# USB-CAN_v0_1.net
KiCad netlist of a schematic drawn in EAGLE
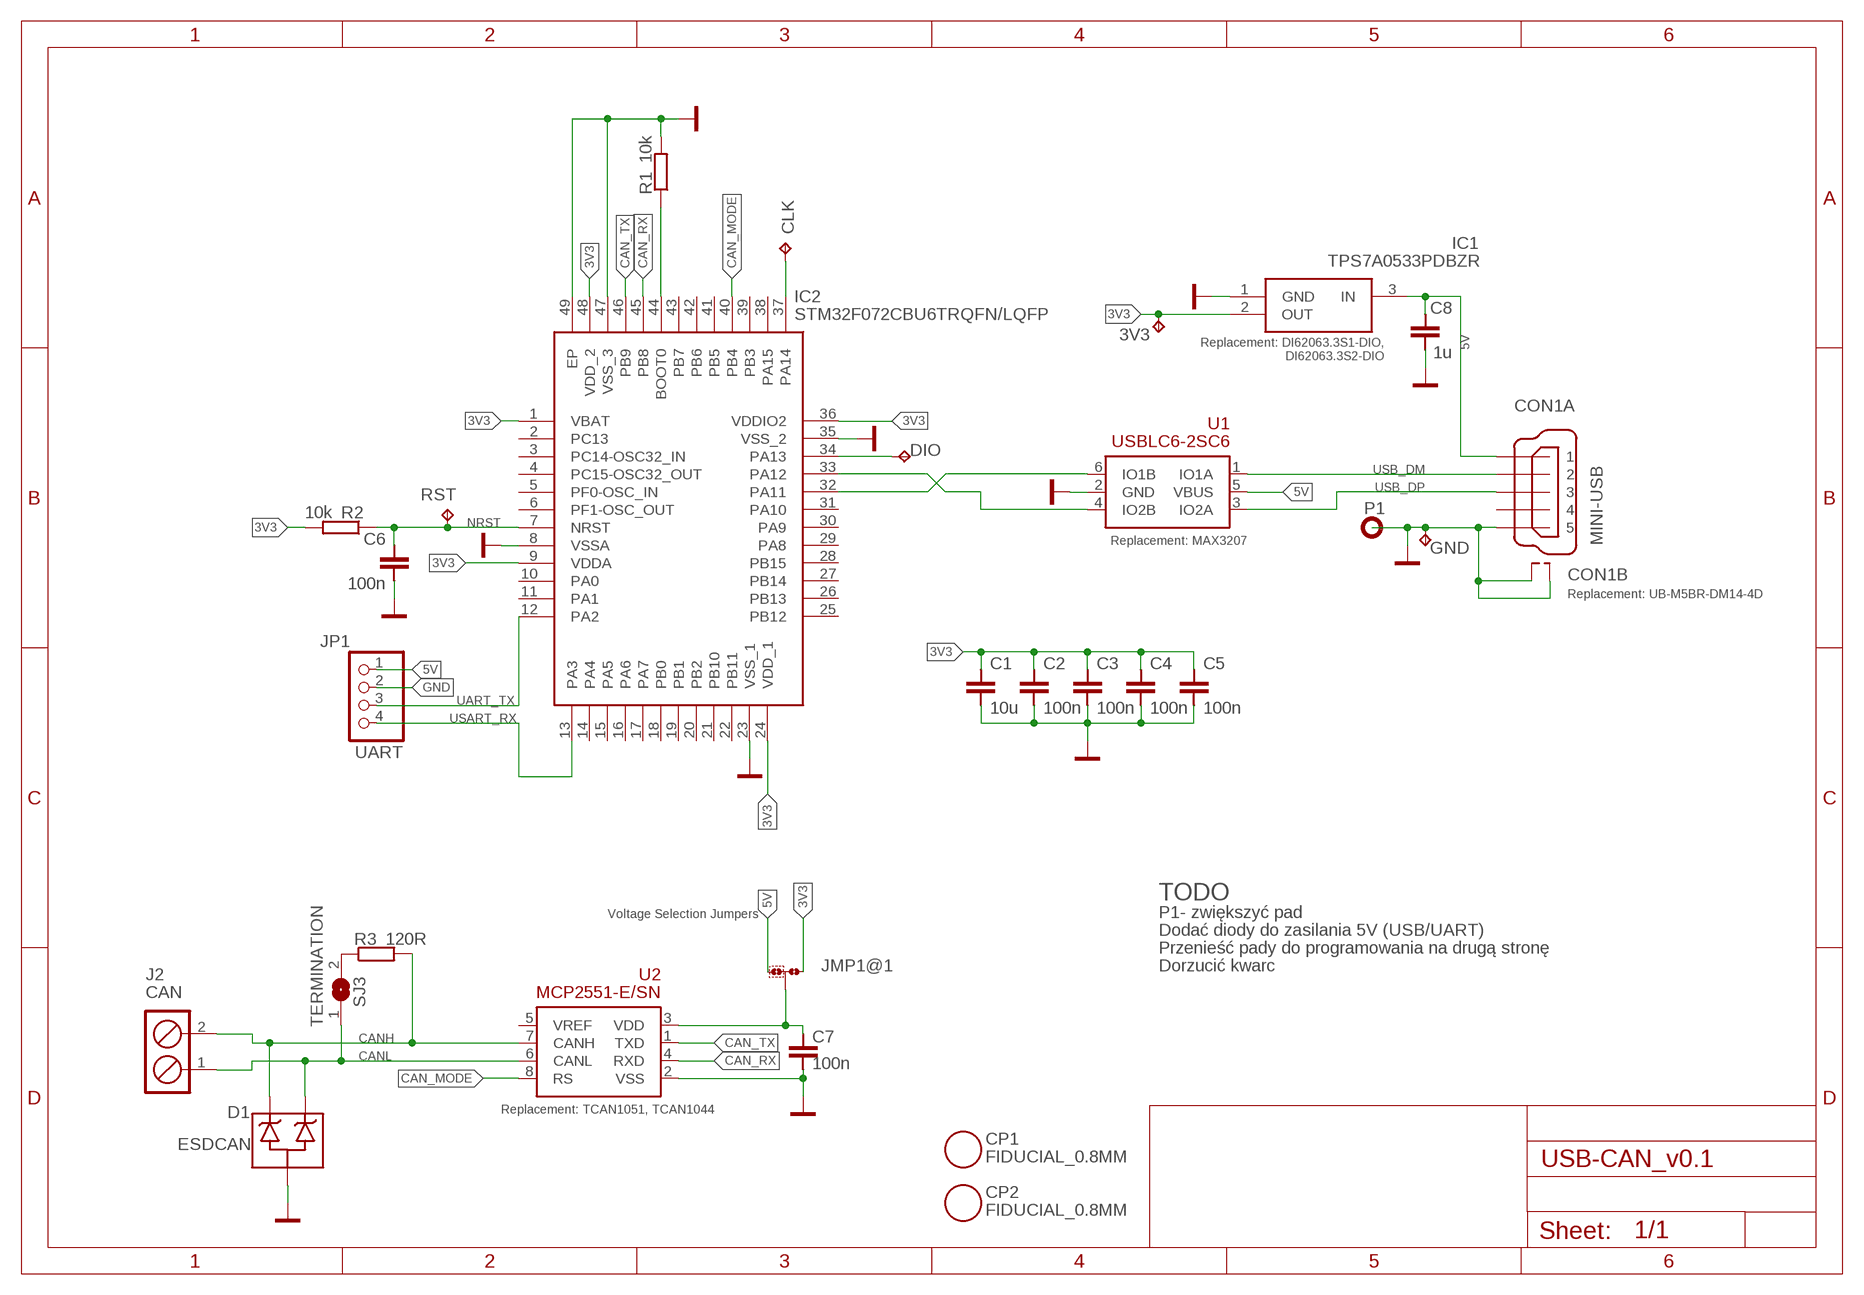
[diagram p0: schematic, sheet 1]

(export (version "E")
  (design (tool "Eeschema 10.0.6"))
  (components
    (comp (ref "3V3")
      (value "TPTP14R")
      (footprint "eagle-import:TP14R")
      (libsource (lib "eagle-import") (part "TPTP14R"))
    )
    (comp (ref "C1")
      (value "10u")
      (footprint "eagle-import:0603")
      (libsource (lib "eagle-import") (part "CAP_H-0603"))
    )
    (comp (ref "C2")
      (value "100n")
      (footprint "eagle-import:0603")
      (libsource (lib "eagle-import") (part "CAP_H-0603"))
    )
    (comp (ref "C3")
      (value "100n")
      (footprint "eagle-import:0603")
      (libsource (lib "eagle-import") (part "CAP_H-0603"))
    )
    (comp (ref "C4")
      (value "100n")
      (footprint "eagle-import:0603")
      (libsource (lib "eagle-import") (part "CAP_H-0603"))
    )
    (comp (ref "C5")
      (value "100n")
      (footprint "eagle-import:0603")
      (libsource (lib "eagle-import") (part "CAP_H-0603"))
    )
    (comp (ref "C6")
      (value "100n")
      (footprint "eagle-import:0603")
      (libsource (lib "eagle-import") (part "CAP_H-0603"))
    )
    (comp (ref "C7")
      (value "100n")
      (footprint "eagle-import:0603")
      (libsource (lib "eagle-import") (part "CAP_H-0603"))
    )
    (comp (ref "C8")
      (value "1u")
      (footprint "eagle-import:0603")
      (libsource (lib "eagle-import") (part "CAP_H-0603"))
    )
    (comp (ref "CLK")
      (value "TPTP14R")
      (footprint "eagle-import:TP14R")
      (libsource (lib "eagle-import") (part "TPTP14R"))
    )
    (comp (ref "CON1")
      (value "MINI-USB")
      (footprint "eagle-import:GMSB0522132EU")
      (libsource (lib "eagle-import") (part "MINI-USB"))
    )
    (comp (ref "CP1")
      (value "FIDUCIAL_0.8MM")
      (footprint "eagle-import:FIDUCIAL_0.8MM_MINI")
      (libsource (lib "eagle-import") (part "FIDUCIAL_0.8MM"))
    )
    (comp (ref "CP2")
      (value "FIDUCIAL_0.8MM")
      (footprint "eagle-import:FIDUCIAL_0.8MM_MINI")
      (libsource (lib "eagle-import") (part "FIDUCIAL_0.8MM"))
    )
    (comp (ref "D1")
      (value "ESDCAN")
      (footprint "eagle-import:SOT323-3L_ST")
      (libsource (lib "eagle-import") (part "TRANSIL-DUO"))
    )
    (comp (ref "DIO")
      (value "TPTP14R")
      (footprint "eagle-import:TP14R")
      (libsource (lib "eagle-import") (part "TPTP14R"))
    )
    (comp (ref "GND")
      (value "TPTP14R")
      (footprint "eagle-import:TP14R")
      (libsource (lib "eagle-import") (part "TPTP14R"))
    )
    (comp (ref "IC1")
      (value "TPS7A0533PDBZR")
      (footprint "eagle-import:SOT23")
      (libsource (lib "eagle-import") (part "TPS7A0533PDBZR"))
    )
    (comp (ref "IC2")
      (value "STM32F072CBU6TRQFN/LQFP")
      (footprint "eagle-import:LQFP_QFN48")
      (libsource (lib "eagle-import") (part "STM32F072CBU6TRQFN/LQFP"))
    )
    (comp (ref "J2")
      (value "CAN")
      (footprint "eagle-import:SRUB_2PIN_5MM")
      (fields (field (name "MPN") "MKDSN 1,5/2-5.08"))
      (libsource (lib "eagle-import") (part "SRUB_2PIN"))
    )
    (comp (ref "JMP1")
      (value "0R-JUMPC")
      (footprint "eagle-import:C0R-JMP")
      (libsource (lib "eagle-import") (part "0R-JUMPC"))
    )
    (comp (ref "JP1")
      (value "UART")
      (footprint "eagle-import:1X04")
      (libsource (lib "eagle-import") (part "PINHD-1X4"))
    )
    (comp (ref "P1")
      (value "PAD1.3")
      (footprint "eagle-import:1,5_0,9")
      (libsource (lib "eagle-import") (part "PAD1.3"))
    )
    (comp (ref "R1")
      (value "10k")
      (footprint "eagle-import:0603")
      (libsource (lib "eagle-import") (part "RES_H-0603"))
    )
    (comp (ref "R2")
      (value "10k")
      (footprint "eagle-import:0603")
      (libsource (lib "eagle-import") (part "RES_H-0603"))
    )
    (comp (ref "R3")
      (value "120R")
      (footprint "eagle-import:0603")
      (libsource (lib "eagle-import") (part "RES_H-0603"))
    )
    (comp (ref "RST")
      (value "TPTP14R")
      (footprint "eagle-import:TP14R")
      (libsource (lib "eagle-import") (part "TPTP14R"))
    )
    (comp (ref "SJ3")
      (value "TERMINATION")
      (footprint "eagle-import:SJ")
      (libsource (lib "eagle-import") (part "SJ"))
    )
    (comp (ref "U1")
      (value "USBLC6-2SC6")
      (footprint "eagle-import:SOT23-6L")
      (libsource (lib "eagle-import") (part "USBLC6-2SC6"))
    )
    (comp (ref "U2")
      (value "MCP2551-E/SN")
      (footprint "eagle-import:SO8")
      (libsource (lib "eagle-import") (part "MCP2551-E/SN"))
    )
  )
  (nets
    (net (code "1") (name "/CANH") (class "Default")
      (node (ref "D1") (pin "2") (pinfunction "2_2") (pintype "passive"))
      (node (ref "J2") (pin "2") (pinfunction "2_2") (pintype "passive"))
      (node (ref "R3") (pin "2") (pinfunction "2_2") (pintype "passive"))
      (node (ref "U2") (pin "7") (pinfunction "CANH_7") (pintype "bidirectional"))
    )
    (net (code "2") (name "/CANL") (class "Default")
      (node (ref "D1") (pin "1") (pinfunction "1_1") (pintype "passive"))
      (node (ref "J2") (pin "1") (pinfunction "1_1") (pintype "passive"))
      (node (ref "SJ3") (pin "1") (pinfunction "1_1") (pintype "passive"))
      (node (ref "U2") (pin "6") (pinfunction "CANL_6") (pintype "bidirectional"))
    )
    (net (code "3") (name "/NRST") (class "Default")
      (node (ref "C6") (pin "1") (pinfunction "1_1") (pintype "passive"))
      (node (ref "IC2") (pin "7") (pinfunction "NRST_7") (pintype "bidirectional"))
      (node (ref "R2") (pin "1") (pinfunction "1_1") (pintype "passive"))
      (node (ref "RST") (pin "TP") (pinfunction "TP_TP") (pintype "input"))
    )
    (net (code "4") (name "/UART_TX") (class "Default")
      (node (ref "IC2") (pin "12") (pinfunction "PA2_12") (pintype "bidirectional"))
      (node (ref "JP1") (pin "3") (pinfunction "3_3") (pintype "passive"))
    )
    (net (code "5") (name "/USART_RX") (class "Default")
      (node (ref "IC2") (pin "13") (pinfunction "PA3_13") (pintype "bidirectional"))
      (node (ref "JP1") (pin "4") (pinfunction "4_4") (pintype "passive"))
    )
    (net (code "6") (name "/USB_DM") (class "Default")
      (node (ref "CON1") (pin "P2") (pinfunction "2_P2") (pintype "passive"))
      (node (ref "U1") (pin "1") (pinfunction "IO1A_1") (pintype "bidirectional"))
    )
    (net (code "7") (name "/USB_DP") (class "Default")
      (node (ref "CON1") (pin "P3") (pinfunction "3_P3") (pintype "passive"))
      (node (ref "U1") (pin "3") (pinfunction "IO2A_3") (pintype "bidirectional"))
    )
    (net (code "8") (name "3V3") (class "Default")
      (node (ref "3V3") (pin "TP") (pinfunction "TP_TP") (pintype "input"))
      (node (ref "C1") (pin "1") (pinfunction "1_1") (pintype "passive"))
      (node (ref "C2") (pin "1") (pinfunction "1_1") (pintype "passive"))
      (node (ref "C3") (pin "1") (pinfunction "1_1") (pintype "passive"))
      (node (ref "C4") (pin "1") (pinfunction "1_1") (pintype "passive"))
      (node (ref "C5") (pin "1") (pinfunction "1_1") (pintype "passive"))
      (node (ref "IC1") (pin "2") (pinfunction "OUT_2") (pintype "output"))
      (node (ref "IC2") (pin "1") (pinfunction "VBAT_1") (pintype "bidirectional"))
      (node (ref "IC2") (pin "24") (pinfunction "VDD_1_24") (pintype "bidirectional"))
      (node (ref "IC2") (pin "36") (pinfunction "VDDIO2_36") (pintype "bidirectional"))
      (node (ref "IC2") (pin "48") (pinfunction "VDD_2_48") (pintype "bidirectional"))
      (node (ref "IC2") (pin "9") (pinfunction "VDDA_9") (pintype "bidirectional"))
      (node (ref "JMP1") (pin "1") (pinfunction "1_1") (pintype "passive"))
      (node (ref "R2") (pin "2") (pinfunction "2_2") (pintype "passive"))
    )
    (net (code "9") (name "5V") (class "Default")
      (node (ref "C8") (pin "1") (pinfunction "1_1") (pintype "passive"))
      (node (ref "CON1") (pin "P1") (pinfunction "1_P1") (pintype "passive"))
      (node (ref "IC1") (pin "3") (pinfunction "IN_3") (pintype "input"))
      (node (ref "JMP1") (pin "3") (pinfunction "3_3") (pintype "passive"))
      (node (ref "JP1") (pin "1") (pinfunction "1_1") (pintype "passive"))
      (node (ref "U1") (pin "5") (pinfunction "VBUS_5") (pintype "bidirectional"))
    )
    (net (code "10") (name "CAN_MODE") (class "Default")
      (node (ref "IC2") (pin "40") (pinfunction "PB4_40") (pintype "bidirectional"))
      (node (ref "U2") (pin "8") (pinfunction "RS_8") (pintype "bidirectional"))
    )
    (net (code "11") (name "CAN_RX") (class "Default")
      (node (ref "IC2") (pin "45") (pinfunction "PB8_45") (pintype "bidirectional"))
      (node (ref "U2") (pin "4") (pinfunction "RXD_4") (pintype "bidirectional"))
    )
    (net (code "12") (name "CAN_TX") (class "Default")
      (node (ref "IC2") (pin "46") (pinfunction "PB9_46") (pintype "bidirectional"))
      (node (ref "U2") (pin "1") (pinfunction "TXD_1") (pintype "bidirectional"))
    )
    (net (code "13") (name "GND") (class "Default")
      (node (ref "C1") (pin "2") (pinfunction "2_2") (pintype "passive"))
      (node (ref "C2") (pin "2") (pinfunction "2_2") (pintype "passive"))
      (node (ref "C3") (pin "2") (pinfunction "2_2") (pintype "passive"))
      (node (ref "C4") (pin "2") (pinfunction "2_2") (pintype "passive"))
      (node (ref "C5") (pin "2") (pinfunction "2_2") (pintype "passive"))
      (node (ref "C6") (pin "2") (pinfunction "2_2") (pintype "passive"))
      (node (ref "C7") (pin "2") (pinfunction "2_2") (pintype "passive"))
      (node (ref "C8") (pin "2") (pinfunction "2_2") (pintype "passive"))
      (node (ref "CON1") (pin "MH1") (pinfunction "S1_MH1") (pintype "passive"))
      (node (ref "CON1") (pin "MH2") (pinfunction "S2_MH2") (pintype "passive"))
      (node (ref "CON1") (pin "P5") (pinfunction "5_P5") (pintype "passive"))
      (node (ref "D1") (pin "3") (pinfunction "3_3") (pintype "passive"))
      (node (ref "GND") (pin "TP") (pinfunction "TP_TP") (pintype "input"))
      (node (ref "IC1") (pin "1") (pinfunction "GND_1") (pintype "power_in"))
      (node (ref "IC2") (pin "23") (pinfunction "VSS_1_23") (pintype "bidirectional"))
      (node (ref "IC2") (pin "35") (pinfunction "VSS_2_35") (pintype "bidirectional"))
      (node (ref "IC2") (pin "47") (pinfunction "VSS_3_47") (pintype "bidirectional"))
      (node (ref "IC2") (pin "49") (pinfunction "EP_49") (pintype "bidirectional"))
      (node (ref "IC2") (pin "8") (pinfunction "VSSA_8") (pintype "bidirectional"))
      (node (ref "JP1") (pin "2") (pinfunction "2_2") (pintype "passive"))
      (node (ref "P1") (pin "1") (pinfunction "P_1") (pintype "passive"))
      (node (ref "R1") (pin "2") (pinfunction "2_2") (pintype "passive"))
      (node (ref "U1") (pin "2") (pinfunction "GND_2") (pintype "bidirectional"))
      (node (ref "U2") (pin "2") (pinfunction "VSS_2") (pintype "bidirectional"))
    )
    (net (code "14") (name "Net-(IC2-BOOT0)") (class "Default")
      (node (ref "IC2") (pin "44") (pinfunction "BOOT0_44") (pintype "bidirectional"))
      (node (ref "R1") (pin "1") (pinfunction "1_1") (pintype "passive"))
    )
    (net (code "15") (name "Net-(IC2-PA11)") (class "Default")
      (node (ref "IC2") (pin "32") (pinfunction "PA11_32") (pintype "bidirectional"))
      (node (ref "U1") (pin "6") (pinfunction "IO1B_6") (pintype "bidirectional"))
    )
    (net (code "16") (name "Net-(IC2-PA12)") (class "Default")
      (node (ref "IC2") (pin "33") (pinfunction "PA12_33") (pintype "bidirectional"))
      (node (ref "U1") (pin "4") (pinfunction "IO2B_4") (pintype "bidirectional"))
    )
    (net (code "17") (name "Net-(IC2-PA13)") (class "Default")
      (node (ref "DIO") (pin "TP") (pinfunction "TP_TP") (pintype "input"))
      (node (ref "IC2") (pin "34") (pinfunction "PA13_34") (pintype "bidirectional"))
    )
    (net (code "18") (name "Net-(IC2-PA14)") (class "Default")
      (node (ref "CLK") (pin "TP") (pinfunction "TP_TP") (pintype "input"))
      (node (ref "IC2") (pin "37") (pinfunction "PA14_37") (pintype "bidirectional"))
    )
    (net (code "19") (name "Net-(R3-Pad1)") (class "Default")
      (node (ref "R3") (pin "1") (pinfunction "1_1") (pintype "passive"))
      (node (ref "SJ3") (pin "2") (pinfunction "2_2") (pintype "passive"))
    )
    (net (code "20") (name "Net-(U2-VDD)") (class "Default")
      (node (ref "C7") (pin "1") (pinfunction "1_1") (pintype "passive"))
      (node (ref "JMP1") (pin "2") (pinfunction "2_2") (pintype "passive"))
      (node (ref "U2") (pin "3") (pinfunction "VDD_3") (pintype "bidirectional"))
    )
    (net (code "21") (name "unconnected-(CON1A-4-PadP4)") (class "Default")
      (node (ref "CON1") (pin "P4") (pinfunction "4_P4") (pintype "passive"))
    )
    (net (code "22") (name "unconnected-(IC2-PA0-Pad10)") (class "Default")
      (node (ref "IC2") (pin "10") (pinfunction "PA0_10") (pintype "bidirectional"))
    )
    (net (code "23") (name "unconnected-(IC2-PA1-Pad11)") (class "Default")
      (node (ref "IC2") (pin "11") (pinfunction "PA1_11") (pintype "bidirectional"))
    )
    (net (code "24") (name "unconnected-(IC2-PA4-Pad14)") (class "Default")
      (node (ref "IC2") (pin "14") (pinfunction "PA4_14") (pintype "bidirectional"))
    )
    (net (code "25") (name "unconnected-(IC2-PA5-Pad15)") (class "Default")
      (node (ref "IC2") (pin "15") (pinfunction "PA5_15") (pintype "bidirectional"))
    )
    (net (code "26") (name "unconnected-(IC2-PA6-Pad16)") (class "Default")
      (node (ref "IC2") (pin "16") (pinfunction "PA6_16") (pintype "bidirectional"))
    )
    (net (code "27") (name "unconnected-(IC2-PA7-Pad17)") (class "Default")
      (node (ref "IC2") (pin "17") (pinfunction "PA7_17") (pintype "bidirectional"))
    )
    (net (code "28") (name "unconnected-(IC2-PA8-Pad29)") (class "Default")
      (node (ref "IC2") (pin "29") (pinfunction "PA8_29") (pintype "bidirectional"))
    )
    (net (code "29") (name "unconnected-(IC2-PA9-Pad30)") (class "Default")
      (node (ref "IC2") (pin "30") (pinfunction "PA9_30") (pintype "bidirectional"))
    )
    (net (code "30") (name "unconnected-(IC2-PA10-Pad31)") (class "Default")
      (node (ref "IC2") (pin "31") (pinfunction "PA10_31") (pintype "bidirectional"))
    )
    (net (code "31") (name "unconnected-(IC2-PA15-Pad38)") (class "Default")
      (node (ref "IC2") (pin "38") (pinfunction "PA15_38") (pintype "bidirectional"))
    )
    (net (code "32") (name "unconnected-(IC2-PB0-Pad18)") (class "Default")
      (node (ref "IC2") (pin "18") (pinfunction "PB0_18") (pintype "bidirectional"))
    )
    (net (code "33") (name "unconnected-(IC2-PB1-Pad19)") (class "Default")
      (node (ref "IC2") (pin "19") (pinfunction "PB1_19") (pintype "bidirectional"))
    )
    (net (code "34") (name "unconnected-(IC2-PB2-Pad20)") (class "Default")
      (node (ref "IC2") (pin "20") (pinfunction "PB2_20") (pintype "bidirectional"))
    )
    (net (code "35") (name "unconnected-(IC2-PB3-Pad39)") (class "Default")
      (node (ref "IC2") (pin "39") (pinfunction "PB3_39") (pintype "bidirectional"))
    )
    (net (code "36") (name "unconnected-(IC2-PB5-Pad41)") (class "Default")
      (node (ref "IC2") (pin "41") (pinfunction "PB5_41") (pintype "bidirectional"))
    )
    (net (code "37") (name "unconnected-(IC2-PB6-Pad42)") (class "Default")
      (node (ref "IC2") (pin "42") (pinfunction "PB6_42") (pintype "bidirectional"))
    )
    (net (code "38") (name "unconnected-(IC2-PB7-Pad43)") (class "Default")
      (node (ref "IC2") (pin "43") (pinfunction "PB7_43") (pintype "bidirectional"))
    )
    (net (code "39") (name "unconnected-(IC2-PB10-Pad21)") (class "Default")
      (node (ref "IC2") (pin "21") (pinfunction "PB10_21") (pintype "bidirectional"))
    )
    (net (code "40") (name "unconnected-(IC2-PB11-Pad22)") (class "Default")
      (node (ref "IC2") (pin "22") (pinfunction "PB11_22") (pintype "bidirectional"))
    )
    (net (code "41") (name "unconnected-(IC2-PB12-Pad25)") (class "Default")
      (node (ref "IC2") (pin "25") (pinfunction "PB12_25") (pintype "bidirectional"))
    )
    (net (code "42") (name "unconnected-(IC2-PB13-Pad26)") (class "Default")
      (node (ref "IC2") (pin "26") (pinfunction "PB13_26") (pintype "bidirectional"))
    )
    (net (code "43") (name "unconnected-(IC2-PB14-Pad27)") (class "Default")
      (node (ref "IC2") (pin "27") (pinfunction "PB14_27") (pintype "bidirectional"))
    )
    (net (code "44") (name "unconnected-(IC2-PB15-Pad28)") (class "Default")
      (node (ref "IC2") (pin "28") (pinfunction "PB15_28") (pintype "bidirectional"))
    )
    (net (code "45") (name "unconnected-(IC2-PC13-Pad2)") (class "Default")
      (node (ref "IC2") (pin "2") (pinfunction "PC13_2") (pintype "bidirectional"))
    )
    (net (code "46") (name "unconnected-(IC2-PC14-OSC32_IN-Pad3)") (class "Default")
      (node (ref "IC2") (pin "3") (pinfunction "PC14-OSC32_IN_3") (pintype "bidirectional"))
    )
    (net (code "47") (name "unconnected-(IC2-PC15-OSC32_OUT-Pad4)") (class "Default")
      (node (ref "IC2") (pin "4") (pinfunction "PC15-OSC32_OUT_4") (pintype "bidirectional"))
    )
    (net (code "48") (name "unconnected-(IC2-PF0-OSC_IN-Pad5)") (class "Default")
      (node (ref "IC2") (pin "5") (pinfunction "PF0-OSC_IN_5") (pintype "bidirectional"))
    )
    (net (code "49") (name "unconnected-(IC2-PF1-OSC_OUT-Pad6)") (class "Default")
      (node (ref "IC2") (pin "6") (pinfunction "PF1-OSC_OUT_6") (pintype "bidirectional"))
    )
    (net (code "50") (name "unconnected-(U2-VREF-Pad5)") (class "Default")
      (node (ref "U2") (pin "5") (pinfunction "VREF_5") (pintype "bidirectional"))
    )
  )
)
